# Get_In_Line_REV1.net
KiCad netlist of a schematic drawn in EAGLE
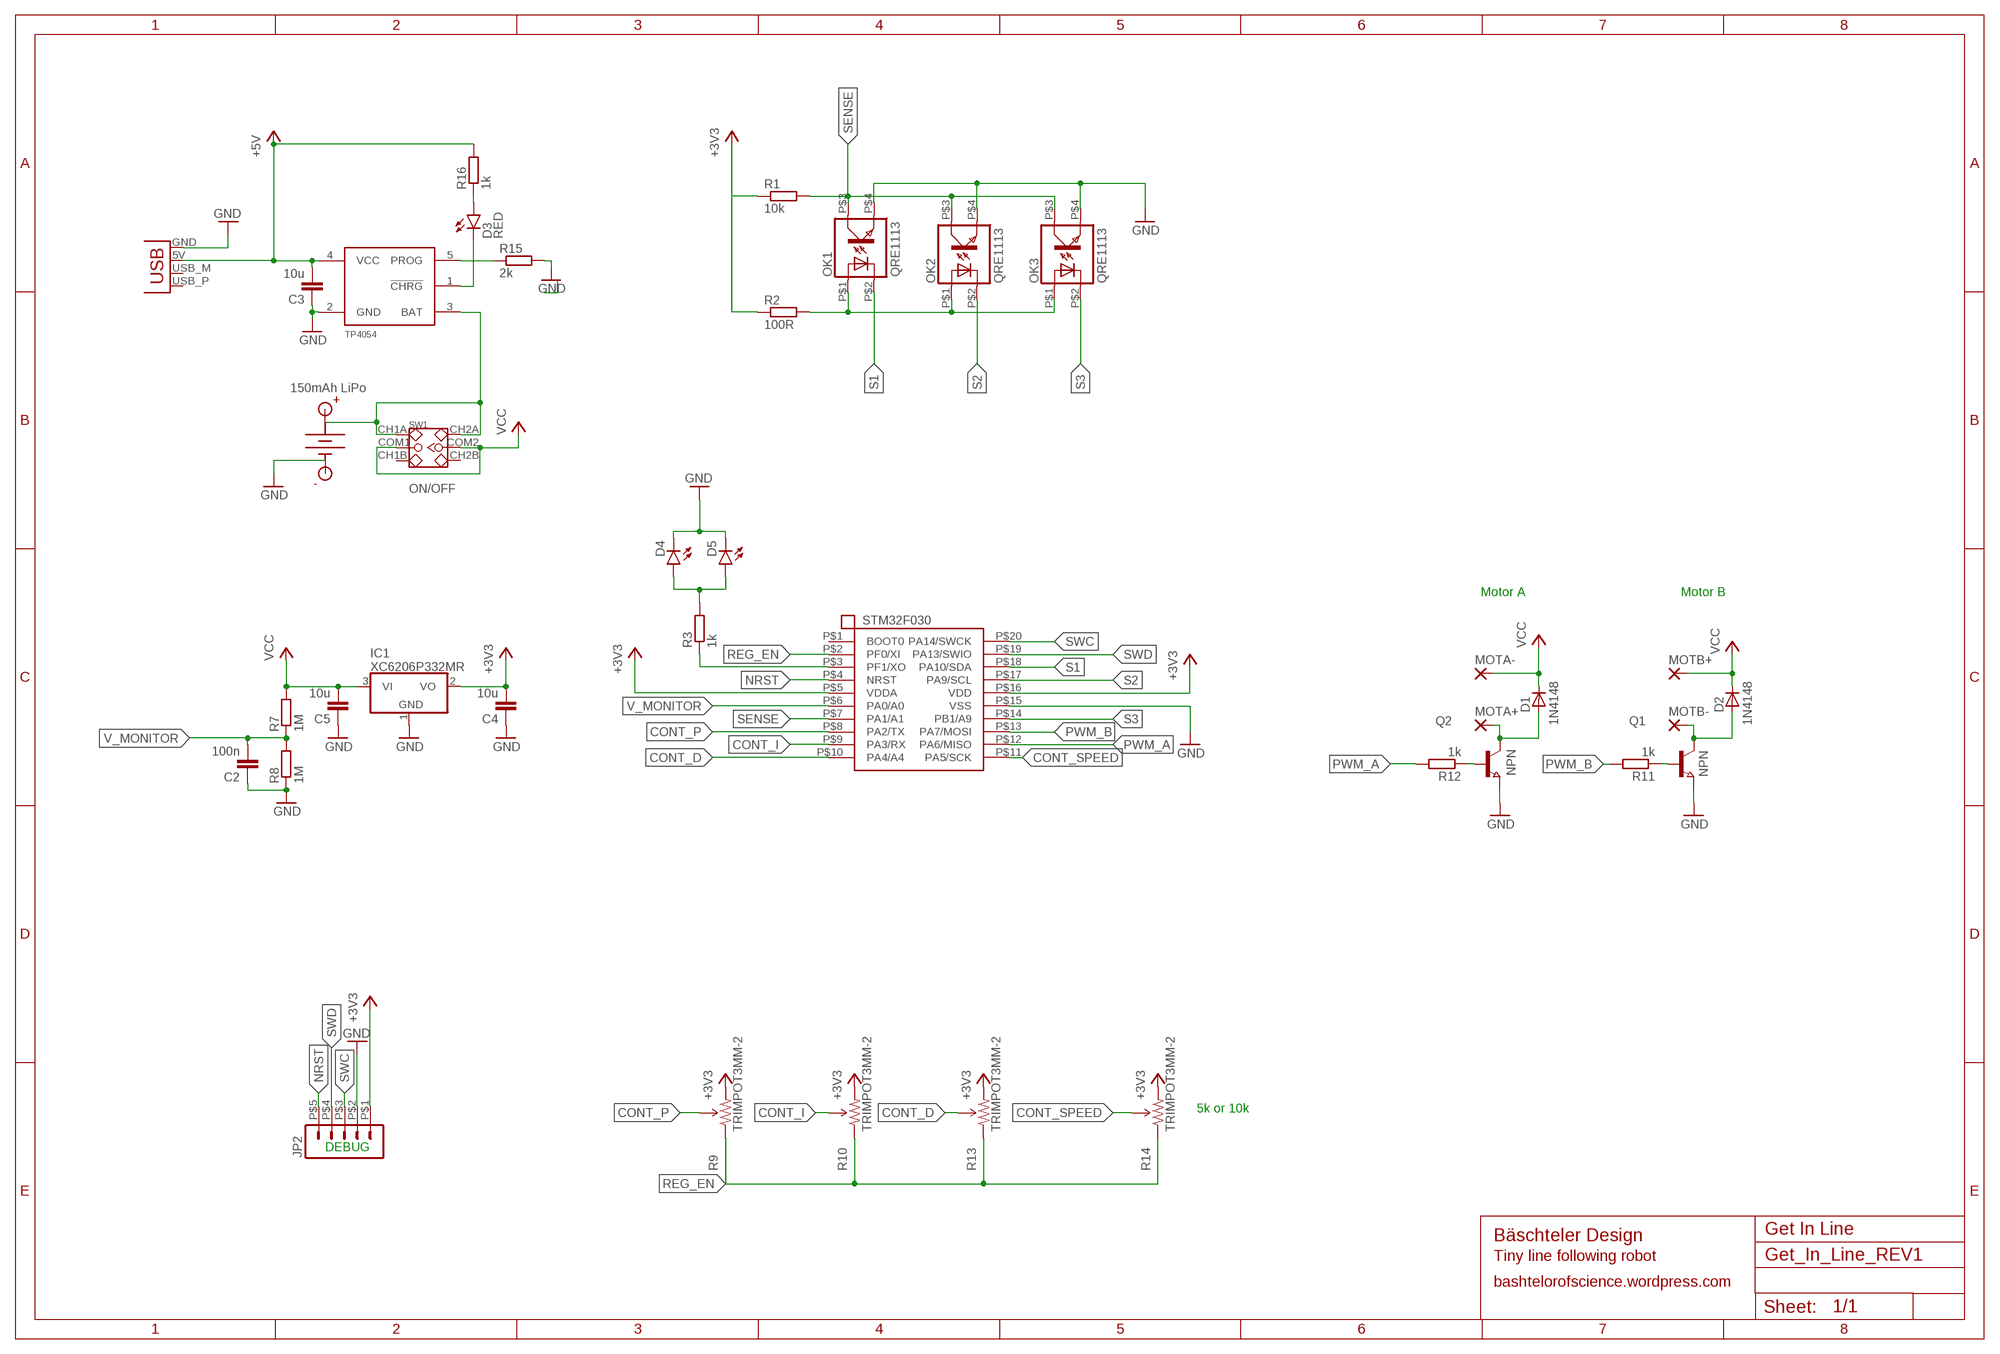
[diagram p0: schematic, sheet 1]

(export (version "E")
  (design (tool "Eeschema 10.0.6"))
  (components
    (comp (ref "C2")
      (value "100n")
      (footprint "eagle-import:C0805")
      (libsource (lib "eagle-import") (part "C-EUC0805"))
    )
    (comp (ref "C3")
      (value "10u")
      (footprint "eagle-import:C0805")
      (libsource (lib "eagle-import") (part "C-EUC0805"))
    )
    (comp (ref "C4")
      (value "10u")
      (footprint "eagle-import:C0805")
      (libsource (lib "eagle-import") (part "C-EUC0805"))
    )
    (comp (ref "C5")
      (value "10u")
      (footprint "eagle-import:C0805")
      (libsource (lib "eagle-import") (part "C-EUC0805"))
    )
    (comp (ref "D1")
      (value "D-SOD-80")
      (footprint "eagle-import:SOD80")
      (libsource (lib "eagle-import") (part "D-SOD-80"))
    )
    (comp (ref "D2")
      (value "D-SOD-80")
      (footprint "eagle-import:SOD80")
      (libsource (lib "eagle-import") (part "D-SOD-80"))
    )
    (comp (ref "D3")
      (value "RED")
      (footprint "eagle-import:LED-1206")
      (libsource (lib "eagle-import") (part "LED-RED1206"))
    )
    (comp (ref "D4")
      (value "GREEN")
      (footprint "eagle-import:LED-1206")
      (libsource (lib "eagle-import") (part "LED-GREENLARGE"))
    )
    (comp (ref "D5")
      (value "GREEN")
      (footprint "eagle-import:LED-1206")
      (libsource (lib "eagle-import") (part "LED-GREENLARGE"))
    )
    (comp (ref "IC1")
      (value "MCP1703CB")
      (footprint "eagle-import:SOT23")
      (libsource (lib "eagle-import") (part "MCP1703CB"))
    )
    (comp (ref "JP1")
      (value "USBPCB")
      (footprint "eagle-import:USB-A-PCB")
      (libsource (lib "eagle-import") (part "USBPCB"))
    )
    (comp (ref "JP2")
      (value "M05")
      (footprint "eagle-import:SMD_HEADER_5P")
      (libsource (lib "eagle-import") (part "M05"))
    )
    (comp (ref "MCU")
      (value "STM32F030F4P6")
      (footprint "eagle-import:TSSOP-20")
      (libsource (lib "eagle-import") (part "STM32F030F4P6"))
    )
    (comp (ref "MOTA+")
      (value "1,6/0,9")
      (footprint "eagle-import:1,6_0,9")
      (libsource (lib "eagle-import") (part "1,6/0,9"))
    )
    (comp (ref "MOTA-")
      (value "1,6/0,9")
      (footprint "eagle-import:1,6_0,9")
      (libsource (lib "eagle-import") (part "1,6/0,9"))
    )
    (comp (ref "MOTB+")
      (value "1,6/0,9")
      (footprint "eagle-import:1,6_0,9")
      (libsource (lib "eagle-import") (part "1,6/0,9"))
    )
    (comp (ref "MOTB-")
      (value "1,6/0,9")
      (footprint "eagle-import:1,6_0,9")
      (libsource (lib "eagle-import") (part "1,6/0,9"))
    )
    (comp (ref "OK1")
      (value "QRE1113")
      (footprint "eagle-import:DIL04")
      (libsource (lib "eagle-import") (part "QRE1113"))
    )
    (comp (ref "OK2")
      (value "QRE1113")
      (footprint "eagle-import:DIL04")
      (libsource (lib "eagle-import") (part "QRE1113"))
    )
    (comp (ref "OK3")
      (value "QRE1113")
      (footprint "eagle-import:DIL04")
      (libsource (lib "eagle-import") (part "QRE1113"))
    )
    (comp (ref "Q1")
      (value "NPN-TRANSISTOR_SOT23")
      (footprint "eagle-import:SOT23")
      (libsource (lib "eagle-import") (part "NPN-TRANSISTOR_SOT23"))
    )
    (comp (ref "Q2")
      (value "NPN-TRANSISTOR_SOT23")
      (footprint "eagle-import:SOT23")
      (libsource (lib "eagle-import") (part "NPN-TRANSISTOR_SOT23"))
    )
    (comp (ref "R1")
      (value "10k")
      (footprint "eagle-import:R0805")
      (libsource (lib "eagle-import") (part "R-EU_R0805"))
    )
    (comp (ref "R2")
      (value "100R")
      (footprint "eagle-import:R0805")
      (libsource (lib "eagle-import") (part "R-EU_R0805"))
    )
    (comp (ref "R3")
      (value "1k")
      (footprint "eagle-import:R0805")
      (libsource (lib "eagle-import") (part "R-EU_R0805"))
    )
    (comp (ref "R7")
      (value "1M")
      (footprint "eagle-import:R0805")
      (libsource (lib "eagle-import") (part "R-EU_R0805"))
    )
    (comp (ref "R8")
      (value "1M")
      (footprint "eagle-import:R0805")
      (libsource (lib "eagle-import") (part "R-EU_R0805"))
    )
    (comp (ref "R9")
      (value "TRIMPOT3MM-2")
      (footprint "eagle-import:TRIMPOT-3MM-2")
      (libsource (lib "eagle-import") (part "TRIMPOT3MM-2"))
    )
    (comp (ref "R10")
      (value "TRIMPOT3MM-2")
      (footprint "eagle-import:TRIMPOT-3MM-2")
      (libsource (lib "eagle-import") (part "TRIMPOT3MM-2"))
    )
    (comp (ref "R11")
      (value "1k")
      (footprint "eagle-import:R0805")
      (libsource (lib "eagle-import") (part "R-EU_R0805"))
    )
    (comp (ref "R12")
      (value "1k")
      (footprint "eagle-import:R0805")
      (libsource (lib "eagle-import") (part "R-EU_R0805"))
    )
    (comp (ref "R13")
      (value "TRIMPOT3MM-2")
      (footprint "eagle-import:TRIMPOT-3MM-2")
      (libsource (lib "eagle-import") (part "TRIMPOT3MM-2"))
    )
    (comp (ref "R14")
      (value "TRIMPOT3MM-2")
      (footprint "eagle-import:TRIMPOT-3MM-2")
      (libsource (lib "eagle-import") (part "TRIMPOT3MM-2"))
    )
    (comp (ref "R15")
      (value "2k")
      (footprint "eagle-import:R0805")
      (libsource (lib "eagle-import") (part "R-EU_R0805"))
    )
    (comp (ref "R16")
      (value "1k")
      (footprint "eagle-import:R0805")
      (libsource (lib "eagle-import") (part "R-EU_R0805"))
    )
    (comp (ref "SW1")
      (value "DIP-TOGGLE-SWITCH-2CH-(2X3P-2.54)")
      (footprint "eagle-import:SW6-2.54-9.0X3.5X3.2+2.0MM")
      (fields (field (name "MPN") "MS-22D18 G2 ROHS"))
      (libsource (lib "eagle-import") (part "DIP-TOGGLE-SWITCH-2CH-(2X3P-2.54)"))
    )
    (comp (ref "U$1")
      (value "TP4054_LIPO_CHARGER")
      (footprint "eagle-import:SOT23-5")
      (libsource (lib "eagle-import") (part "TP4054_LIPO_CHARGER"))
    )
    (comp (ref "U$5")
      (value "BATTERY_PAD+1.5MM")
      (footprint "eagle-import:LIPO_BATTERY_PADS_1.5MM")
      (libsource (lib "eagle-import") (part "BATTERY_PAD+1.5MM"))
    )
    (comp (ref "U$6")
      (value "BATTERY_PAD-1.5MM")
      (footprint "eagle-import:LIPO_BATTERY_PADS_1.5MM")
      (libsource (lib "eagle-import") (part "BATTERY_PAD-1.5MM"))
    )
  )
  (nets
    (net (code "1") (name "+3V3") (class "Default")
      (node (ref "C4") (pin "2") (pinfunction "2_2") (pintype "passive"))
      (node (ref "IC1") (pin "2") (pinfunction "VO_2") (pintype "passive"))
      (node (ref "JP2") (pin "P$1") (pinfunction "1_P$1") (pintype "passive"))
      (node (ref "MCU") (pin "P$16") (pinfunction "VDD_P$16") (pintype "bidirectional"))
      (node (ref "MCU") (pin "P$5") (pinfunction "VDDA_P$5") (pintype "bidirectional"))
      (node (ref "R1") (pin "1") (pinfunction "1_1") (pintype "passive"))
      (node (ref "R10") (pin "3") (pinfunction "CW_3") (pintype "passive"))
      (node (ref "R13") (pin "3") (pinfunction "CW_3") (pintype "passive"))
      (node (ref "R14") (pin "3") (pinfunction "CW_3") (pintype "passive"))
      (node (ref "R2") (pin "1") (pinfunction "1_1") (pintype "passive"))
      (node (ref "R9") (pin "3") (pinfunction "CW_3") (pintype "passive"))
    )
    (net (code "2") (name "+5V") (class "Default")
      (node (ref "C3") (pin "2") (pinfunction "2_2") (pintype "passive"))
      (node (ref "JP1") (pin "5V") (pinfunction "VBUS_5V") (pintype "bidirectional"))
      (node (ref "R16") (pin "2") (pinfunction "2_2") (pintype "passive"))
      (node (ref "U$1") (pin "4") (pinfunction "VCC_4") (pintype "bidirectional"))
    )
    (net (code "3") (name "CONT_D") (class "Default")
      (node (ref "MCU") (pin "P$10") (pinfunction "PA4/A4_P$10") (pintype "bidirectional"))
      (node (ref "R13") (pin "2") (pinfunction "WIPER_2") (pintype "passive"))
    )
    (net (code "4") (name "CONT_I") (class "Default")
      (node (ref "MCU") (pin "P$9") (pinfunction "PA3/RX_P$9") (pintype "bidirectional"))
      (node (ref "R10") (pin "2") (pinfunction "WIPER_2") (pintype "passive"))
    )
    (net (code "5") (name "CONT_P") (class "Default")
      (node (ref "MCU") (pin "P$8") (pinfunction "PA2/TX_P$8") (pintype "bidirectional"))
      (node (ref "R9") (pin "2") (pinfunction "WIPER_2") (pintype "passive"))
    )
    (net (code "6") (name "CONT_SPEED") (class "Default")
      (node (ref "MCU") (pin "P$11") (pinfunction "PA5/SCK_P$11") (pintype "bidirectional"))
      (node (ref "R14") (pin "2") (pinfunction "WIPER_2") (pintype "passive"))
    )
    (net (code "7") (name "GND") (class "Default")
      (node (ref "C2") (pin "1") (pinfunction "1_1") (pintype "passive"))
      (node (ref "C3") (pin "1") (pinfunction "1_1") (pintype "passive"))
      (node (ref "C4") (pin "1") (pinfunction "1_1") (pintype "passive"))
      (node (ref "C5") (pin "1") (pinfunction "1_1") (pintype "passive"))
      (node (ref "D4") (pin "C") (pinfunction "C_C") (pintype "passive"))
      (node (ref "D5") (pin "C") (pinfunction "C_C") (pintype "passive"))
      (node (ref "IC1") (pin "1") (pinfunction "GND_1") (pintype "passive"))
      (node (ref "JP1") (pin "GND") (pinfunction "GND_GND") (pintype "bidirectional"))
      (node (ref "JP2") (pin "P$2") (pinfunction "2_P$2") (pintype "passive"))
      (node (ref "MCU") (pin "P$15") (pinfunction "VSS_P$15") (pintype "bidirectional"))
      (node (ref "OK1") (pin "P$4") (pinfunction "EMIT_P$4") (pintype "passive"))
      (node (ref "OK2") (pin "P$4") (pinfunction "EMIT_P$4") (pintype "passive"))
      (node (ref "OK3") (pin "P$4") (pinfunction "EMIT_P$4") (pintype "passive"))
      (node (ref "Q1") (pin "2") (pinfunction "E_2") (pintype "passive"))
      (node (ref "Q2") (pin "2") (pinfunction "E_2") (pintype "passive"))
      (node (ref "R15") (pin "2") (pinfunction "2_2") (pintype "passive"))
      (node (ref "R8") (pin "1") (pinfunction "1_1") (pintype "passive"))
      (node (ref "U$1") (pin "2") (pinfunction "GND_2") (pintype "bidirectional"))
      (node (ref "U$6") (pin "P$1") (pinfunction "P$1_P$1") (pintype "bidirectional"))
    )
    (net (code "8") (name "NRST") (class "Default")
      (node (ref "JP2") (pin "P$5") (pinfunction "5_P$5") (pintype "passive"))
      (node (ref "MCU") (pin "P$4") (pinfunction "NRST_P$4") (pintype "bidirectional"))
    )
    (net (code "9") (name "Net-(D1-A)") (class "Default")
      (node (ref "D1") (pin "2") (pinfunction "A_2") (pintype "passive"))
      (node (ref "MOTA+") (pin "1") (pinfunction "P_1") (pintype "passive"))
      (node (ref "Q2") (pin "3") (pinfunction "C_3") (pintype "passive"))
    )
    (net (code "10") (name "Net-(D2-A)") (class "Default")
      (node (ref "D2") (pin "2") (pinfunction "A_2") (pintype "passive"))
      (node (ref "MOTB-") (pin "1") (pinfunction "P_1") (pintype "passive"))
      (node (ref "Q1") (pin "3") (pinfunction "C_3") (pintype "passive"))
    )
    (net (code "11") (name "Net-(D3-PadA)") (class "Default")
      (node (ref "D3") (pin "A") (pinfunction "A_A") (pintype "passive"))
      (node (ref "R16") (pin "1") (pinfunction "1_1") (pintype "passive"))
    )
    (net (code "12") (name "Net-(D4-PadA)") (class "Default")
      (node (ref "D4") (pin "A") (pinfunction "A_A") (pintype "passive"))
      (node (ref "D5") (pin "A") (pinfunction "A_A") (pintype "passive"))
      (node (ref "R3") (pin "2") (pinfunction "2_2") (pintype "passive"))
    )
    (net (code "13") (name "Net-(MCU-PF1{slash}XO)") (class "Default")
      (node (ref "MCU") (pin "P$3") (pinfunction "PF1/XO_P$3") (pintype "bidirectional"))
      (node (ref "R3") (pin "1") (pinfunction "1_1") (pintype "passive"))
    )
    (net (code "14") (name "Net-(OK1-A)") (class "Default")
      (node (ref "OK1") (pin "P$1") (pinfunction "A_P$1") (pintype "passive"))
      (node (ref "OK2") (pin "P$1") (pinfunction "A_P$1") (pintype "passive"))
      (node (ref "OK3") (pin "P$1") (pinfunction "A_P$1") (pintype "passive"))
      (node (ref "R2") (pin "2") (pinfunction "2_2") (pintype "passive"))
    )
    (net (code "15") (name "Net-(Q1-B)") (class "Default")
      (node (ref "Q1") (pin "1") (pinfunction "B_1") (pintype "passive"))
      (node (ref "R11") (pin "1") (pinfunction "1_1") (pintype "passive"))
    )
    (net (code "16") (name "Net-(Q2-B)") (class "Default")
      (node (ref "Q2") (pin "1") (pinfunction "B_1") (pintype "passive"))
      (node (ref "R12") (pin "1") (pinfunction "1_1") (pintype "passive"))
    )
    (net (code "17") (name "Net-(U$1-BAT)") (class "Default")
      (node (ref "SW1") (pin "CH1A") (pinfunction "CH1A_CH1A") (pintype "bidirectional"))
      (node (ref "SW1") (pin "CH2A") (pinfunction "CH2A_CH2A") (pintype "bidirectional"))
      (node (ref "U$1") (pin "3") (pinfunction "BAT_3") (pintype "bidirectional"))
      (node (ref "U$5") (pin "P$1") (pinfunction "P$1_P$1") (pintype "bidirectional"))
    )
    (net (code "18") (name "Net-(U$1-PROG)") (class "Default")
      (node (ref "R15") (pin "1") (pinfunction "1_1") (pintype "passive"))
      (node (ref "U$1") (pin "5") (pinfunction "PROG_5") (pintype "bidirectional"))
    )
    (net (code "19") (name "Net-(U$1-~{CHRG})") (class "Default")
      (node (ref "D3") (pin "C") (pinfunction "C_C") (pintype "passive"))
      (node (ref "U$1") (pin "1") (pinfunction "~{CHRG}_1") (pintype "bidirectional"))
    )
    (net (code "20") (name "PWM_A") (class "Default")
      (node (ref "MCU") (pin "P$12") (pinfunction "PA6/MISO_P$12") (pintype "bidirectional"))
      (node (ref "R12") (pin "2") (pinfunction "2_2") (pintype "passive"))
    )
    (net (code "21") (name "PWM_B") (class "Default")
      (node (ref "MCU") (pin "P$13") (pinfunction "PA7/MOSI_P$13") (pintype "bidirectional"))
      (node (ref "R11") (pin "2") (pinfunction "2_2") (pintype "passive"))
    )
    (net (code "22") (name "REG_EN") (class "Default")
      (node (ref "MCU") (pin "P$2") (pinfunction "PF0/XI_P$2") (pintype "bidirectional"))
      (node (ref "R10") (pin "1") (pinfunction "CCW_1") (pintype "passive"))
      (node (ref "R13") (pin "1") (pinfunction "CCW_1") (pintype "passive"))
      (node (ref "R14") (pin "1") (pinfunction "CCW_1") (pintype "passive"))
      (node (ref "R9") (pin "1") (pinfunction "CCW_1") (pintype "passive"))
    )
    (net (code "23") (name "S1") (class "Default")
      (node (ref "MCU") (pin "P$18") (pinfunction "PA10/SDA_P$18") (pintype "bidirectional"))
      (node (ref "OK1") (pin "P$2") (pinfunction "C_P$2") (pintype "passive"))
    )
    (net (code "24") (name "S2") (class "Default")
      (node (ref "MCU") (pin "P$17") (pinfunction "PA9/SCL_P$17") (pintype "bidirectional"))
      (node (ref "OK2") (pin "P$2") (pinfunction "C_P$2") (pintype "passive"))
    )
    (net (code "25") (name "S3") (class "Default")
      (node (ref "MCU") (pin "P$14") (pinfunction "PB1/A9_P$14") (pintype "bidirectional"))
      (node (ref "OK3") (pin "P$2") (pinfunction "C_P$2") (pintype "passive"))
    )
    (net (code "26") (name "SENSE") (class "Default")
      (node (ref "MCU") (pin "P$7") (pinfunction "PA1/A1_P$7") (pintype "bidirectional"))
      (node (ref "OK1") (pin "P$3") (pinfunction "COL_P$3") (pintype "passive"))
      (node (ref "OK2") (pin "P$3") (pinfunction "COL_P$3") (pintype "passive"))
      (node (ref "OK3") (pin "P$3") (pinfunction "COL_P$3") (pintype "passive"))
      (node (ref "R1") (pin "2") (pinfunction "2_2") (pintype "passive"))
    )
    (net (code "27") (name "SWC") (class "Default")
      (node (ref "JP2") (pin "P$3") (pinfunction "3_P$3") (pintype "passive"))
      (node (ref "MCU") (pin "P$20") (pinfunction "PA14/SWCK_P$20") (pintype "bidirectional"))
    )
    (net (code "28") (name "SWD") (class "Default")
      (node (ref "JP2") (pin "P$4") (pinfunction "4_P$4") (pintype "passive"))
      (node (ref "MCU") (pin "P$19") (pinfunction "PA13/SWIO_P$19") (pintype "bidirectional"))
    )
    (net (code "29") (name "VCC") (class "Default")
      (node (ref "C5") (pin "2") (pinfunction "2_2") (pintype "passive"))
      (node (ref "D1") (pin "1") (pinfunction "C_1") (pintype "passive"))
      (node (ref "D2") (pin "1") (pinfunction "C_1") (pintype "passive"))
      (node (ref "IC1") (pin "3") (pinfunction "VI_3") (pintype "input"))
      (node (ref "MOTA-") (pin "1") (pinfunction "P_1") (pintype "passive"))
      (node (ref "MOTB+") (pin "1") (pinfunction "P_1") (pintype "passive"))
      (node (ref "R7") (pin "2") (pinfunction "2_2") (pintype "passive"))
      (node (ref "SW1") (pin "COM1") (pinfunction "COM1_COM1") (pintype "bidirectional"))
      (node (ref "SW1") (pin "COM2") (pinfunction "COM2_COM2") (pintype "bidirectional"))
    )
    (net (code "30") (name "V_MONITOR") (class "Default")
      (node (ref "C2") (pin "2") (pinfunction "2_2") (pintype "passive"))
      (node (ref "MCU") (pin "P$6") (pinfunction "PA0/A0_P$6") (pintype "bidirectional"))
      (node (ref "R7") (pin "1") (pinfunction "1_1") (pintype "passive"))
      (node (ref "R8") (pin "2") (pinfunction "2_2") (pintype "passive"))
    )
    (net (code "31") (name "unconnected-(JP1-D+-PadUSB_P)") (class "Default")
      (node (ref "JP1") (pin "USB_P") (pinfunction "D+_USB_P") (pintype "bidirectional"))
    )
    (net (code "32") (name "unconnected-(JP1-D--PadUSB_M)") (class "Default")
      (node (ref "JP1") (pin "USB_M") (pinfunction "D-_USB_M") (pintype "bidirectional"))
    )
    (net (code "33") (name "unconnected-(MCU-BOOT0-PadP$1)") (class "Default")
      (node (ref "MCU") (pin "P$1") (pinfunction "BOOT0_P$1") (pintype "bidirectional"))
    )
    (net (code "34") (name "unconnected-(SW1-PadCH1B)") (class "Default")
      (node (ref "SW1") (pin "CH1B") (pinfunction "CH1B_CH1B") (pintype "bidirectional"))
    )
    (net (code "35") (name "unconnected-(SW1-PadCH2B)") (class "Default")
      (node (ref "SW1") (pin "CH2B") (pinfunction "CH2B_CH2B") (pintype "bidirectional"))
    )
  )
)
